# CAN_Tranceiver.net
KiCad netlist of a schematic drawn in Altium Designer
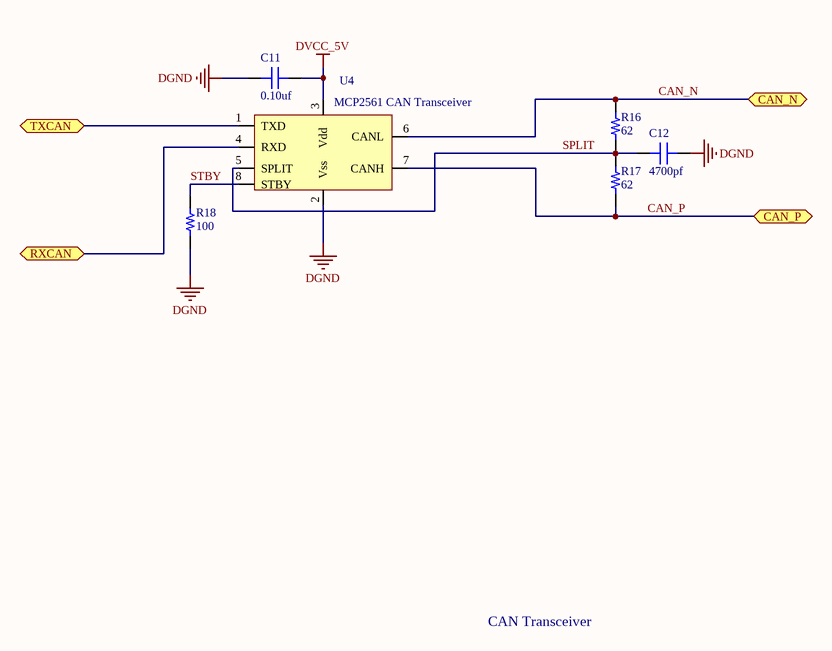
[diagram p0: CAN_Tranceiver.SchDoc]

(export (version "E")
  (design (tool "Eeschema 10.0.6"))
  (components
    (comp (ref "C11")
      (value "0.10uf")
      (footprint "CAP 0603/1608")
      (fields
        (field (name "Comment") "Capacitor MLCC 0.10uf 50V CAP 0603/1608")
        (field (name "CREATED_BY") "Nick Mah")
      )
      (libsource (lib "Altium-Lib") (part "Capacitor"))
    )
    (comp (ref "C12")
      (value "4700pf")
      (footprint "CAP 0603/1608")
      (fields
        (field (name "Comment") "Capacitor MLCC 4700pf 50V CAP 0603/1608")
        (field (name "CREATED_BY") "Nick Mah")
      )
      (libsource (lib "Altium-Lib") (part "Capacitor"))
    )
    (comp (ref "R16")
      (value "62")
      (footprint "RES 0603/1608")
      (fields
        (field (name "TOLERANCE") "5%")
        (field (name "POWER") "1/10W")
        (field (name "Comment") "Resistor 62 0603 1/10W 5%")
        (field (name "CREATED_BY") "Nick Mah")
      )
      (libsource (lib "Altium-Lib") (part "Resistor"))
    )
    (comp (ref "R17")
      (value "62")
      (footprint "RES 0603/1608")
      (fields
        (field (name "TOLERANCE") "5%")
        (field (name "POWER") "1/10W")
        (field (name "Comment") "Resistor 62 0603 1/10W 5%")
        (field (name "CREATED_BY") "Nick Mah")
      )
      (libsource (lib "Altium-Lib") (part "Resistor"))
    )
    (comp (ref "R18")
      (value "100")
      (footprint "RES 0603/1608")
      (fields
        (field (name "TOLERANCE") "10%")
        (field (name "POWER") "1/10W")
        (field (name "Comment") "Resistor 100 0603 1/10W 10%")
        (field (name "CREATED_BY") "Nick Mah")
      )
      (libsource (lib "Altium-Lib") (part "Resistor"))
    )
    (comp (ref "U4")
      (value "MCP2561 CAN Transceiver")
      (footprint "SOIC-8")
      (fields (field (name "MFRPARTNO") "MCP2561") (field (name "CREATED_BY") "Angel Delgado"))
      (libsource (lib "Altium-Lib") (part "MCP2561 CAN Transceiver"))
    )
  )
  (nets
    (net (code "1") (name "/CAN_N") (class "Default")
      (node (ref "R16") (pin "1") (pinfunction "1_1") (pintype "passive"))
      (node (ref "U4") (pin "6") (pinfunction "CANL_6") (pintype "passive"))
    )
    (net (code "2") (name "/CAN_P") (class "Default")
      (node (ref "R17") (pin "2") (pinfunction "2_2") (pintype "passive"))
      (node (ref "U4") (pin "7") (pinfunction "CANH_7") (pintype "passive"))
    )
    (net (code "3") (name "/RXCAN") (class "Default")
      (node (ref "U4") (pin "4") (pinfunction "RXD_4") (pintype "passive"))
    )
    (net (code "4") (name "/SPLIT") (class "Default")
      (node (ref "C12") (pin "2") (pinfunction "2_2") (pintype "passive"))
      (node (ref "R16") (pin "2") (pinfunction "2_2") (pintype "passive"))
      (node (ref "R17") (pin "1") (pinfunction "1_1") (pintype "passive"))
      (node (ref "U4") (pin "5") (pinfunction "SPLIT_5") (pintype "passive"))
    )
    (net (code "5") (name "/STBY") (class "Default")
      (node (ref "R18") (pin "2") (pinfunction "2_2") (pintype "passive"))
      (node (ref "U4") (pin "8") (pinfunction "STBY_8") (pintype "passive"))
    )
    (net (code "6") (name "/TXCAN") (class "Default")
      (node (ref "U4") (pin "1") (pinfunction "TXD_1") (pintype "passive"))
    )
    (net (code "7") (name "DGND") (class "Default")
      (node (ref "C11") (pin "1") (pinfunction "1_1") (pintype "passive"))
      (node (ref "C12") (pin "1") (pinfunction "1_1") (pintype "passive"))
      (node (ref "R18") (pin "1") (pinfunction "1_1") (pintype "passive"))
      (node (ref "U4") (pin "2") (pinfunction "Vss_2") (pintype "passive"))
    )
    (net (code "8") (name "DVCC_5V") (class "Default")
      (node (ref "C11") (pin "2") (pinfunction "2_2") (pintype "passive"))
      (node (ref "U4") (pin "3") (pinfunction "Vdd_3") (pintype "passive"))
    )
  )
)
